# rectifier.net
KiCad netlist of a schematic drawn in Altium Designer
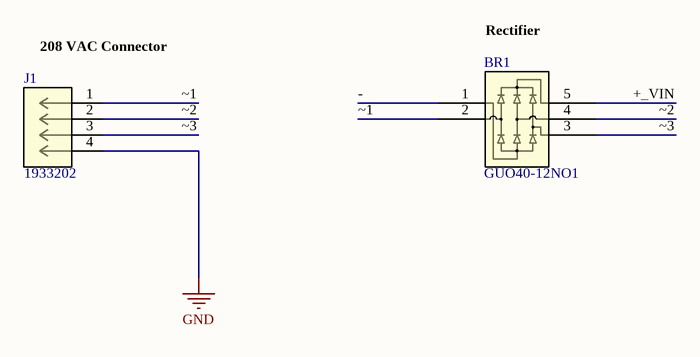
[diagram p0: rectifier.SchDoc]

(export (version "E")
  (design (tool "Eeschema 10.0.6"))
  (components
    (comp (ref "BR1")
      (value "GUO40-12NO1")
      (footprint "SIP5-GUFP_LTF")
      (description "No Description Available")
      (libsource (lib "GUO40-12NO1") (part "GUO40-12NO1"))
    )
    (comp (ref "J1")
      (value "1933202")
      (footprint "CONN_1933202_PXC")
      (description "No Description Available")
      (libsource (lib "1933202") (part "1933202"))
    )
  )
  (nets
    (net (code "1") (name "/+_VIN") (class "Default")
      (node (ref "BR1") (pin "5") (pinfunction "5_5") (pintype "passive"))
    )
    (net (code "2") (name "/-") (class "Default")
      (node (ref "BR1") (pin "1") (pinfunction "1_1") (pintype "passive"))
    )
    (net (code "3") (name "/~1") (class "Default")
      (node (ref "BR1") (pin "2") (pinfunction "2_2") (pintype "passive"))
      (node (ref "J1") (pin "1") (pinfunction "1_1") (pintype "passive"))
    )
    (net (code "4") (name "/~2") (class "Default")
      (node (ref "BR1") (pin "4") (pinfunction "4_4") (pintype "passive"))
      (node (ref "J1") (pin "2") (pinfunction "2_2") (pintype "passive"))
    )
    (net (code "5") (name "/~3") (class "Default")
      (node (ref "BR1") (pin "3") (pinfunction "3_3") (pintype "passive"))
      (node (ref "J1") (pin "3") (pinfunction "3_3") (pintype "passive"))
    )
    (net (code "6") (name "GND") (class "Default")
      (node (ref "J1") (pin "4") (pinfunction "4_4") (pintype "passive"))
    )
  )
)
